# probes_breakout_box_make-before-break.net
KiCad netlist of a schematic drawn in EAGLE
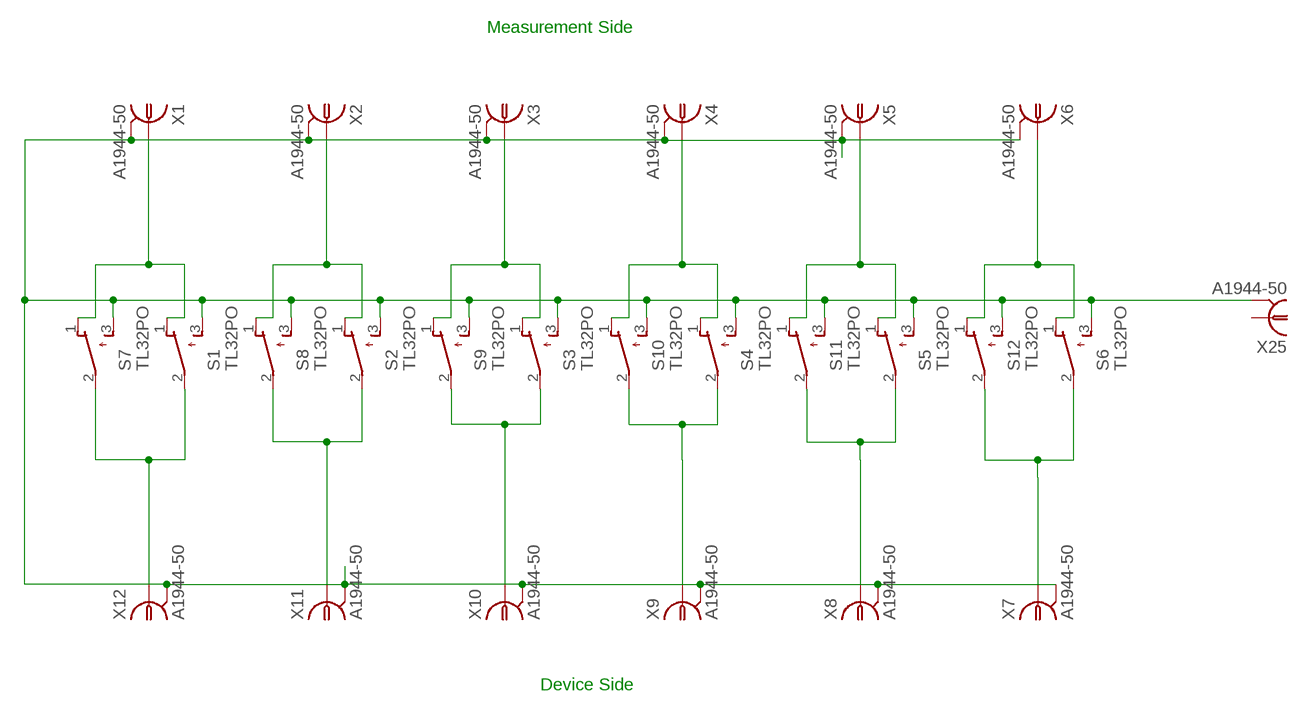
[diagram p0: schematic, sheet 1]

(export (version "E")
  (design (tool "Eeschema 10.0.6"))
  (components
    (comp (ref "S1")
      (value "TL32PO")
      (footprint "eagle-import:TL3XPO")
      (libsource (lib "eagle-import") (part "TL32PO"))
    )
    (comp (ref "S2")
      (value "TL32PO")
      (footprint "eagle-import:TL3XPO")
      (libsource (lib "eagle-import") (part "TL32PO"))
    )
    (comp (ref "S3")
      (value "TL32PO")
      (footprint "eagle-import:TL3XPO")
      (libsource (lib "eagle-import") (part "TL32PO"))
    )
    (comp (ref "S4")
      (value "TL32PO")
      (footprint "eagle-import:TL3XPO")
      (libsource (lib "eagle-import") (part "TL32PO"))
    )
    (comp (ref "S5")
      (value "TL32PO")
      (footprint "eagle-import:TL3XPO")
      (libsource (lib "eagle-import") (part "TL32PO"))
    )
    (comp (ref "S6")
      (value "TL32PO")
      (footprint "eagle-import:TL3XPO")
      (libsource (lib "eagle-import") (part "TL32PO"))
    )
    (comp (ref "S7")
      (value "TL32PO")
      (footprint "eagle-import:TL3XPO")
      (libsource (lib "eagle-import") (part "TL32PO"))
    )
    (comp (ref "S8")
      (value "TL32PO")
      (footprint "eagle-import:TL3XPO")
      (libsource (lib "eagle-import") (part "TL32PO"))
    )
    (comp (ref "S9")
      (value "TL32PO")
      (footprint "eagle-import:TL3XPO")
      (libsource (lib "eagle-import") (part "TL32PO"))
    )
    (comp (ref "S10")
      (value "TL32PO")
      (footprint "eagle-import:TL3XPO")
      (libsource (lib "eagle-import") (part "TL32PO"))
    )
    (comp (ref "S11")
      (value "TL32PO")
      (footprint "eagle-import:TL3XPO")
      (libsource (lib "eagle-import") (part "TL32PO"))
    )
    (comp (ref "S12")
      (value "TL32PO")
      (footprint "eagle-import:TL3XPO")
      (libsource (lib "eagle-import") (part "TL32PO"))
    )
    (comp (ref "X1")
      (value "A1944-50")
      (footprint "eagle-import:A1944")
      (libsource (lib "eagle-import") (part "A1944-50"))
    )
    (comp (ref "X2")
      (value "A1944-50")
      (footprint "eagle-import:A1944")
      (libsource (lib "eagle-import") (part "A1944-50"))
    )
    (comp (ref "X3")
      (value "A1944-50")
      (footprint "eagle-import:A1944")
      (libsource (lib "eagle-import") (part "A1944-50"))
    )
    (comp (ref "X4")
      (value "A1944-50")
      (footprint "eagle-import:A1944")
      (libsource (lib "eagle-import") (part "A1944-50"))
    )
    (comp (ref "X5")
      (value "A1944-50")
      (footprint "eagle-import:A1944")
      (libsource (lib "eagle-import") (part "A1944-50"))
    )
    (comp (ref "X6")
      (value "A1944-50")
      (footprint "eagle-import:A1944")
      (libsource (lib "eagle-import") (part "A1944-50"))
    )
    (comp (ref "X7")
      (value "A1944-50")
      (footprint "eagle-import:A1944")
      (libsource (lib "eagle-import") (part "A1944-50"))
    )
    (comp (ref "X8")
      (value "A1944-50")
      (footprint "eagle-import:A1944")
      (libsource (lib "eagle-import") (part "A1944-50"))
    )
    (comp (ref "X9")
      (value "A1944-50")
      (footprint "eagle-import:A1944")
      (libsource (lib "eagle-import") (part "A1944-50"))
    )
    (comp (ref "X10")
      (value "A1944-50")
      (footprint "eagle-import:A1944")
      (libsource (lib "eagle-import") (part "A1944-50"))
    )
    (comp (ref "X11")
      (value "A1944-50")
      (footprint "eagle-import:A1944")
      (libsource (lib "eagle-import") (part "A1944-50"))
    )
    (comp (ref "X12")
      (value "A1944-50")
      (footprint "eagle-import:A1944")
      (libsource (lib "eagle-import") (part "A1944-50"))
    )
    (comp (ref "X25")
      (value "A1944-50")
      (footprint "eagle-import:A1944")
      (libsource (lib "eagle-import") (part "A1944-50"))
    )
  )
  (nets
    (net (code "1") (name "Net-(S1-O)") (class "Default")
      (node (ref "S1") (pin "1") (pinfunction "O_1") (pintype "passive"))
      (node (ref "S7") (pin "1") (pinfunction "O_1") (pintype "passive"))
      (node (ref "X1") (pin "1") (pinfunction "1_1") (pintype "passive"))
    )
    (net (code "2") (name "Net-(S1-P)") (class "Default")
      (node (ref "S1") (pin "2") (pinfunction "P_2") (pintype "passive"))
      (node (ref "S7") (pin "2") (pinfunction "P_2") (pintype "passive"))
      (node (ref "X12") (pin "1") (pinfunction "1_1") (pintype "passive"))
    )
    (net (code "3") (name "Net-(S1-S)") (class "Default")
      (node (ref "S1") (pin "3") (pinfunction "S_3") (pintype "passive"))
      (node (ref "S10") (pin "3") (pinfunction "S_3") (pintype "passive"))
      (node (ref "S11") (pin "3") (pinfunction "S_3") (pintype "passive"))
      (node (ref "S12") (pin "3") (pinfunction "S_3") (pintype "passive"))
      (node (ref "S2") (pin "3") (pinfunction "S_3") (pintype "passive"))
      (node (ref "S3") (pin "3") (pinfunction "S_3") (pintype "passive"))
      (node (ref "S4") (pin "3") (pinfunction "S_3") (pintype "passive"))
      (node (ref "S5") (pin "3") (pinfunction "S_3") (pintype "passive"))
      (node (ref "S6") (pin "3") (pinfunction "S_3") (pintype "passive"))
      (node (ref "S7") (pin "3") (pinfunction "S_3") (pintype "passive"))
      (node (ref "S8") (pin "3") (pinfunction "S_3") (pintype "passive"))
      (node (ref "S9") (pin "3") (pinfunction "S_3") (pintype "passive"))
      (node (ref "X1") (pin "2") (pinfunction "2_2") (pintype "passive"))
      (node (ref "X1") (pin "3") (pinfunction "2_3") (pintype "passive"))
      (node (ref "X1") (pin "4") (pinfunction "2_4") (pintype "passive"))
      (node (ref "X1") (pin "5") (pinfunction "2_5") (pintype "passive"))
      (node (ref "X10") (pin "2") (pinfunction "2_2") (pintype "passive"))
      (node (ref "X10") (pin "3") (pinfunction "2_3") (pintype "passive"))
      (node (ref "X10") (pin "4") (pinfunction "2_4") (pintype "passive"))
      (node (ref "X10") (pin "5") (pinfunction "2_5") (pintype "passive"))
      (node (ref "X11") (pin "2") (pinfunction "2_2") (pintype "passive"))
      (node (ref "X11") (pin "3") (pinfunction "2_3") (pintype "passive"))
      (node (ref "X11") (pin "4") (pinfunction "2_4") (pintype "passive"))
      (node (ref "X11") (pin "5") (pinfunction "2_5") (pintype "passive"))
      (node (ref "X12") (pin "2") (pinfunction "2_2") (pintype "passive"))
      (node (ref "X12") (pin "3") (pinfunction "2_3") (pintype "passive"))
      (node (ref "X12") (pin "4") (pinfunction "2_4") (pintype "passive"))
      (node (ref "X12") (pin "5") (pinfunction "2_5") (pintype "passive"))
      (node (ref "X2") (pin "2") (pinfunction "2_2") (pintype "passive"))
      (node (ref "X2") (pin "3") (pinfunction "2_3") (pintype "passive"))
      (node (ref "X2") (pin "4") (pinfunction "2_4") (pintype "passive"))
      (node (ref "X2") (pin "5") (pinfunction "2_5") (pintype "passive"))
      (node (ref "X25") (pin "2") (pinfunction "2_2") (pintype "passive"))
      (node (ref "X25") (pin "3") (pinfunction "2_3") (pintype "passive"))
      (node (ref "X25") (pin "4") (pinfunction "2_4") (pintype "passive"))
      (node (ref "X25") (pin "5") (pinfunction "2_5") (pintype "passive"))
      (node (ref "X3") (pin "2") (pinfunction "2_2") (pintype "passive"))
      (node (ref "X3") (pin "3") (pinfunction "2_3") (pintype "passive"))
      (node (ref "X3") (pin "4") (pinfunction "2_4") (pintype "passive"))
      (node (ref "X3") (pin "5") (pinfunction "2_5") (pintype "passive"))
      (node (ref "X4") (pin "2") (pinfunction "2_2") (pintype "passive"))
      (node (ref "X4") (pin "3") (pinfunction "2_3") (pintype "passive"))
      (node (ref "X4") (pin "4") (pinfunction "2_4") (pintype "passive"))
      (node (ref "X4") (pin "5") (pinfunction "2_5") (pintype "passive"))
      (node (ref "X5") (pin "2") (pinfunction "2_2") (pintype "passive"))
      (node (ref "X5") (pin "3") (pinfunction "2_3") (pintype "passive"))
      (node (ref "X5") (pin "4") (pinfunction "2_4") (pintype "passive"))
      (node (ref "X5") (pin "5") (pinfunction "2_5") (pintype "passive"))
      (node (ref "X6") (pin "2") (pinfunction "2_2") (pintype "passive"))
      (node (ref "X6") (pin "3") (pinfunction "2_3") (pintype "passive"))
      (node (ref "X6") (pin "4") (pinfunction "2_4") (pintype "passive"))
      (node (ref "X6") (pin "5") (pinfunction "2_5") (pintype "passive"))
      (node (ref "X7") (pin "2") (pinfunction "2_2") (pintype "passive"))
      (node (ref "X7") (pin "3") (pinfunction "2_3") (pintype "passive"))
      (node (ref "X7") (pin "4") (pinfunction "2_4") (pintype "passive"))
      (node (ref "X7") (pin "5") (pinfunction "2_5") (pintype "passive"))
      (node (ref "X8") (pin "2") (pinfunction "2_2") (pintype "passive"))
      (node (ref "X8") (pin "3") (pinfunction "2_3") (pintype "passive"))
      (node (ref "X8") (pin "4") (pinfunction "2_4") (pintype "passive"))
      (node (ref "X8") (pin "5") (pinfunction "2_5") (pintype "passive"))
      (node (ref "X9") (pin "2") (pinfunction "2_2") (pintype "passive"))
      (node (ref "X9") (pin "3") (pinfunction "2_3") (pintype "passive"))
      (node (ref "X9") (pin "4") (pinfunction "2_4") (pintype "passive"))
      (node (ref "X9") (pin "5") (pinfunction "2_5") (pintype "passive"))
    )
    (net (code "4") (name "Net-(S2-O)") (class "Default")
      (node (ref "S2") (pin "1") (pinfunction "O_1") (pintype "passive"))
      (node (ref "S8") (pin "1") (pinfunction "O_1") (pintype "passive"))
      (node (ref "X2") (pin "1") (pinfunction "1_1") (pintype "passive"))
    )
    (net (code "5") (name "Net-(S2-P)") (class "Default")
      (node (ref "S2") (pin "2") (pinfunction "P_2") (pintype "passive"))
      (node (ref "S8") (pin "2") (pinfunction "P_2") (pintype "passive"))
      (node (ref "X11") (pin "1") (pinfunction "1_1") (pintype "passive"))
    )
    (net (code "6") (name "Net-(S3-O)") (class "Default")
      (node (ref "S3") (pin "1") (pinfunction "O_1") (pintype "passive"))
      (node (ref "S9") (pin "1") (pinfunction "O_1") (pintype "passive"))
      (node (ref "X3") (pin "1") (pinfunction "1_1") (pintype "passive"))
    )
    (net (code "7") (name "Net-(S3-P)") (class "Default")
      (node (ref "S3") (pin "2") (pinfunction "P_2") (pintype "passive"))
      (node (ref "S9") (pin "2") (pinfunction "P_2") (pintype "passive"))
      (node (ref "X10") (pin "1") (pinfunction "1_1") (pintype "passive"))
    )
    (net (code "8") (name "Net-(S10-O)") (class "Default")
      (node (ref "S10") (pin "1") (pinfunction "O_1") (pintype "passive"))
      (node (ref "S4") (pin "1") (pinfunction "O_1") (pintype "passive"))
      (node (ref "X4") (pin "1") (pinfunction "1_1") (pintype "passive"))
    )
    (net (code "9") (name "Net-(S10-P)") (class "Default")
      (node (ref "S10") (pin "2") (pinfunction "P_2") (pintype "passive"))
      (node (ref "S4") (pin "2") (pinfunction "P_2") (pintype "passive"))
      (node (ref "X9") (pin "1") (pinfunction "1_1") (pintype "passive"))
    )
    (net (code "10") (name "Net-(S11-O)") (class "Default")
      (node (ref "S11") (pin "1") (pinfunction "O_1") (pintype "passive"))
      (node (ref "S5") (pin "1") (pinfunction "O_1") (pintype "passive"))
      (node (ref "X5") (pin "1") (pinfunction "1_1") (pintype "passive"))
    )
    (net (code "11") (name "Net-(S11-P)") (class "Default")
      (node (ref "S11") (pin "2") (pinfunction "P_2") (pintype "passive"))
      (node (ref "S5") (pin "2") (pinfunction "P_2") (pintype "passive"))
      (node (ref "X8") (pin "1") (pinfunction "1_1") (pintype "passive"))
    )
    (net (code "12") (name "Net-(S12-O)") (class "Default")
      (node (ref "S12") (pin "1") (pinfunction "O_1") (pintype "passive"))
      (node (ref "S6") (pin "1") (pinfunction "O_1") (pintype "passive"))
      (node (ref "X6") (pin "1") (pinfunction "1_1") (pintype "passive"))
    )
    (net (code "13") (name "Net-(S12-P)") (class "Default")
      (node (ref "S12") (pin "2") (pinfunction "P_2") (pintype "passive"))
      (node (ref "S6") (pin "2") (pinfunction "P_2") (pintype "passive"))
      (node (ref "X7") (pin "1") (pinfunction "1_1") (pintype "passive"))
    )
    (net (code "14") (name "unconnected-(X25-Pad1)") (class "Default")
      (node (ref "X25") (pin "1") (pinfunction "1_1") (pintype "passive"))
    )
  )
)
